# adder.net
KiCad netlist of a schematic drawn in EAGLE
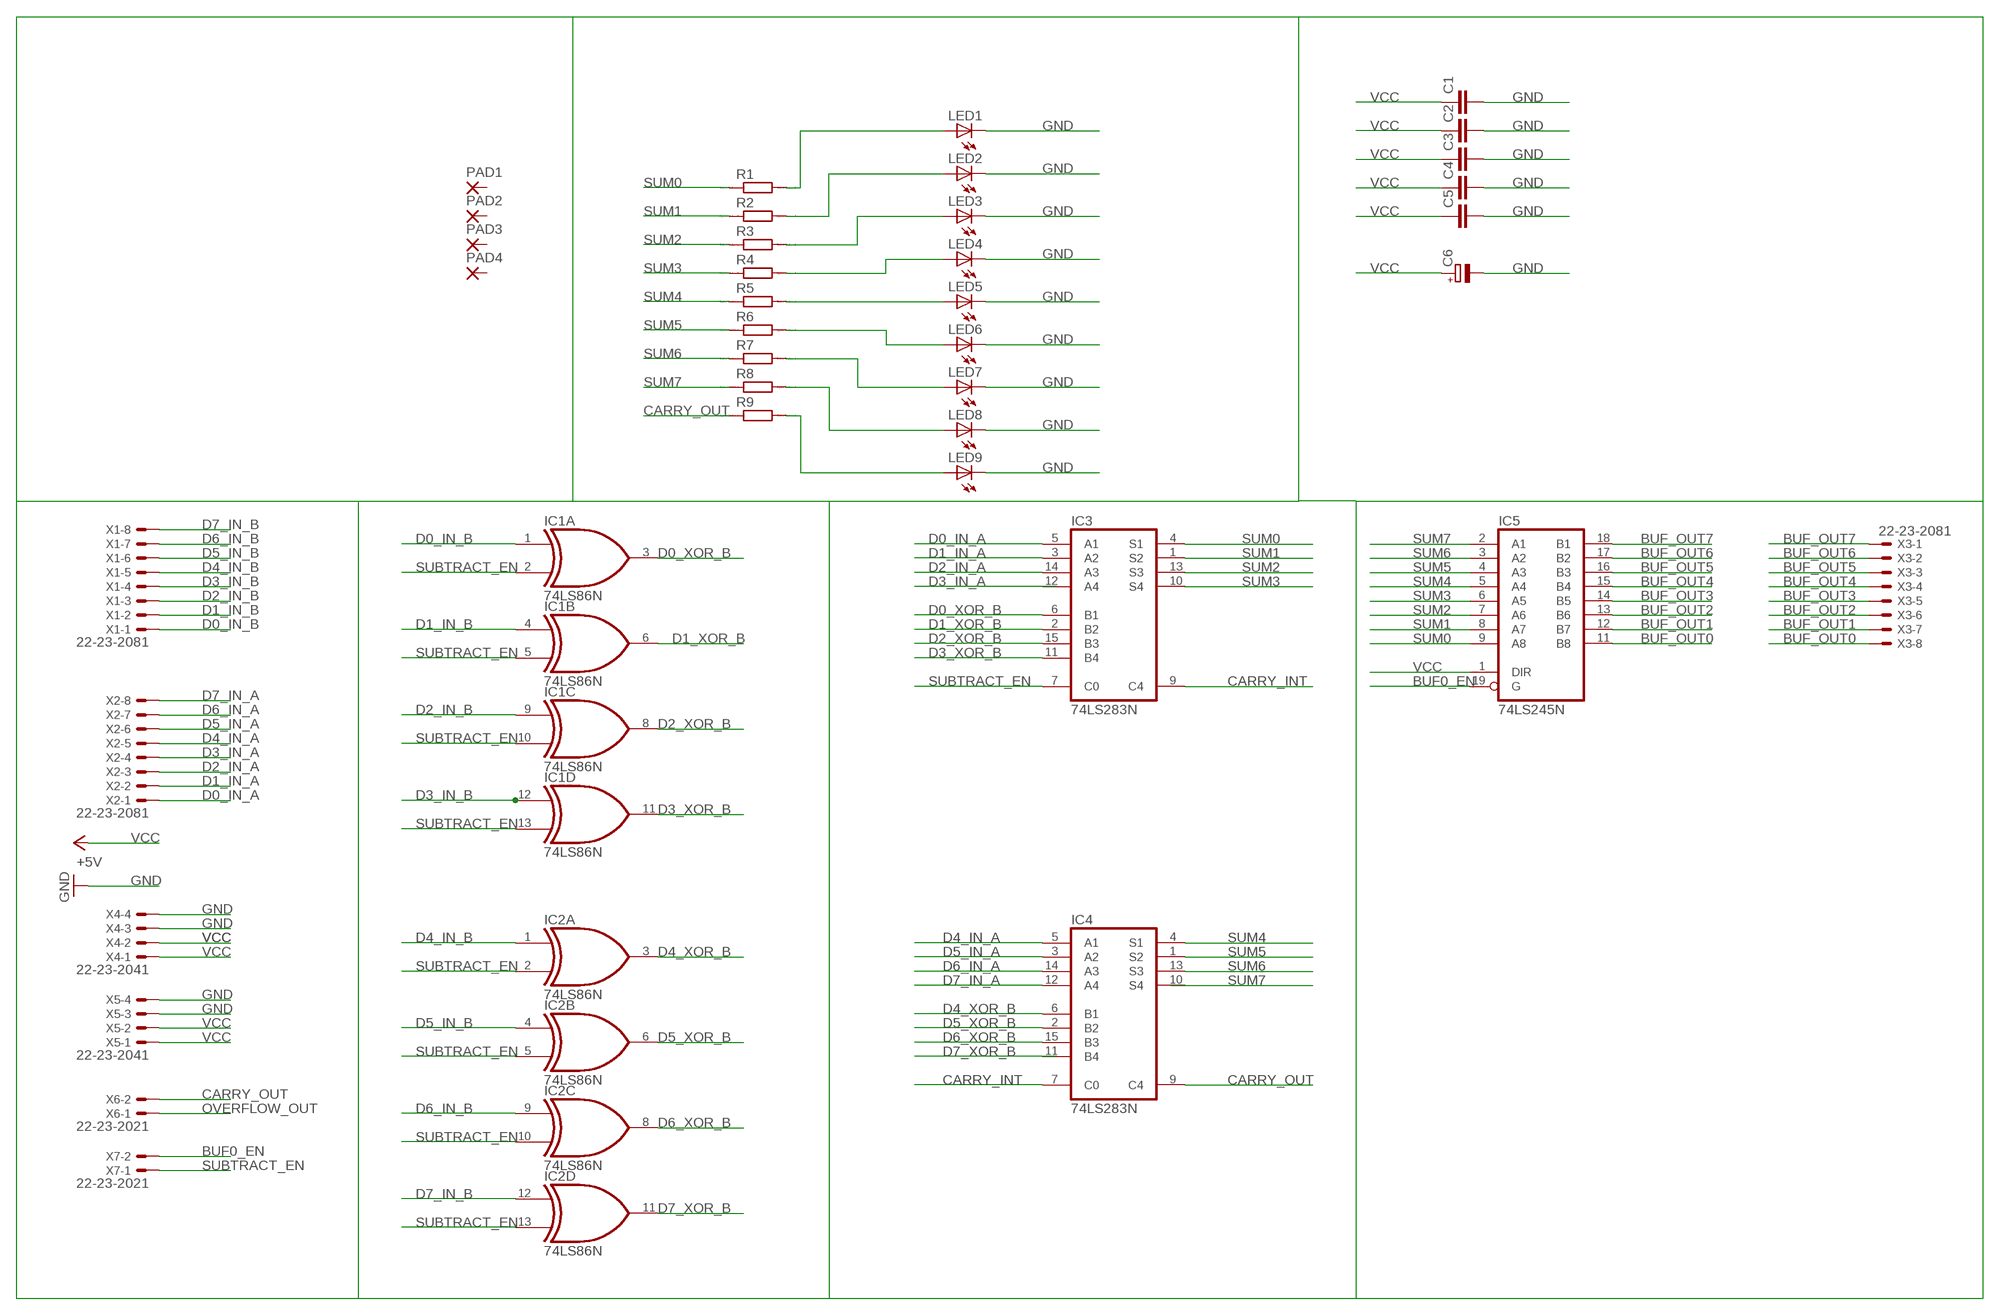
[diagram p0: schematic, sheet 1]

(export (version "E")
  (design (tool "Eeschema 10.0.6"))
  (components
    (comp (ref "C1")
      (value "C-EU025-025X050")
      (footprint "eagle-import:C025-025X050")
      (libsource (lib "eagle-import") (part "C-EU025-025X050"))
    )
    (comp (ref "C2")
      (value "C-EU025-025X050")
      (footprint "eagle-import:C025-025X050")
      (libsource (lib "eagle-import") (part "C-EU025-025X050"))
    )
    (comp (ref "C3")
      (value "C-EU025-025X050")
      (footprint "eagle-import:C025-025X050")
      (libsource (lib "eagle-import") (part "C-EU025-025X050"))
    )
    (comp (ref "C4")
      (value "C-EU025-025X050")
      (footprint "eagle-import:C025-025X050")
      (libsource (lib "eagle-import") (part "C-EU025-025X050"))
    )
    (comp (ref "C5")
      (value "C-EU025-025X050")
      (footprint "eagle-import:C025-025X050")
      (libsource (lib "eagle-import") (part "C-EU025-025X050"))
    )
    (comp (ref "C6")
      (value "CPOL-EUE2.5-6")
      (footprint "eagle-import:E2,5-6")
      (libsource (lib "eagle-import") (part "CPOL-EUE2.5-6"))
    )
    (comp (ref "IC1")
      (value "74LS86N")
      (footprint "eagle-import:DIL14")
      (libsource (lib "eagle-import") (part "7486NLS"))
    )
    (comp (ref "IC2")
      (value "74LS86N")
      (footprint "eagle-import:DIL14")
      (libsource (lib "eagle-import") (part "7486NLS"))
    )
    (comp (ref "IC3")
      (value "74LS283N")
      (footprint "eagle-import:DIL16")
      (libsource (lib "eagle-import") (part "74283NLS"))
    )
    (comp (ref "IC4")
      (value "74LS283N")
      (footprint "eagle-import:DIL16")
      (libsource (lib "eagle-import") (part "74283NLS"))
    )
    (comp (ref "IC5")
      (value "74LS245N")
      (footprint "eagle-import:DIL20")
      (libsource (lib "eagle-import") (part "74245NLS"))
    )
    (comp (ref "LED1")
      (value "LED5MM")
      (footprint "eagle-import:LED5MM")
      (libsource (lib "eagle-import") (part "LED5MM"))
    )
    (comp (ref "LED2")
      (value "LED5MM")
      (footprint "eagle-import:LED5MM")
      (libsource (lib "eagle-import") (part "LED5MM"))
    )
    (comp (ref "LED3")
      (value "LED5MM")
      (footprint "eagle-import:LED5MM")
      (libsource (lib "eagle-import") (part "LED5MM"))
    )
    (comp (ref "LED4")
      (value "LED5MM")
      (footprint "eagle-import:LED5MM")
      (libsource (lib "eagle-import") (part "LED5MM"))
    )
    (comp (ref "LED5")
      (value "LED5MM")
      (footprint "eagle-import:LED5MM")
      (libsource (lib "eagle-import") (part "LED5MM"))
    )
    (comp (ref "LED6")
      (value "LED5MM")
      (footprint "eagle-import:LED5MM")
      (libsource (lib "eagle-import") (part "LED5MM"))
    )
    (comp (ref "LED7")
      (value "LED5MM")
      (footprint "eagle-import:LED5MM")
      (libsource (lib "eagle-import") (part "LED5MM"))
    )
    (comp (ref "LED8")
      (value "LED5MM")
      (footprint "eagle-import:LED5MM")
      (libsource (lib "eagle-import") (part "LED5MM"))
    )
    (comp (ref "LED9")
      (value "LED5MM")
      (footprint "eagle-import:LED5MM")
      (libsource (lib "eagle-import") (part "LED5MM"))
    )
    (comp (ref "PAD1")
      (value "3,17/1,3")
      (footprint "eagle-import:3,17_1,3")
      (libsource (lib "eagle-import") (part "3,17/1,3"))
    )
    (comp (ref "PAD2")
      (value "3,17/1,3")
      (footprint "eagle-import:3,17_1,3")
      (libsource (lib "eagle-import") (part "3,17/1,3"))
    )
    (comp (ref "PAD3")
      (value "3,17/1,3")
      (footprint "eagle-import:3,17_1,3")
      (libsource (lib "eagle-import") (part "3,17/1,3"))
    )
    (comp (ref "PAD4")
      (value "3,17/1,3")
      (footprint "eagle-import:3,17_1,3")
      (libsource (lib "eagle-import") (part "3,17/1,3"))
    )
    (comp (ref "R1")
      (value "R0207/10")
      (footprint "eagle-import:0207_10")
      (libsource (lib "eagle-import") (part "R0207/10"))
    )
    (comp (ref "R2")
      (value "R0207/10")
      (footprint "eagle-import:0207_10")
      (libsource (lib "eagle-import") (part "R0207/10"))
    )
    (comp (ref "R3")
      (value "R0207/10")
      (footprint "eagle-import:0207_10")
      (libsource (lib "eagle-import") (part "R0207/10"))
    )
    (comp (ref "R4")
      (value "R0207/10")
      (footprint "eagle-import:0207_10")
      (libsource (lib "eagle-import") (part "R0207/10"))
    )
    (comp (ref "R5")
      (value "R0207/10")
      (footprint "eagle-import:0207_10")
      (libsource (lib "eagle-import") (part "R0207/10"))
    )
    (comp (ref "R6")
      (value "R0207/10")
      (footprint "eagle-import:0207_10")
      (libsource (lib "eagle-import") (part "R0207/10"))
    )
    (comp (ref "R7")
      (value "R0207/10")
      (footprint "eagle-import:0207_10")
      (libsource (lib "eagle-import") (part "R0207/10"))
    )
    (comp (ref "R8")
      (value "R0207/10")
      (footprint "eagle-import:0207_10")
      (libsource (lib "eagle-import") (part "R0207/10"))
    )
    (comp (ref "R9")
      (value "R0207/10")
      (footprint "eagle-import:0207_10")
      (libsource (lib "eagle-import") (part "R0207/10"))
    )
    (comp (ref "X1")
      (value "22-23-2081")
      (footprint "eagle-import:22-23-2081")
      (fields (field (name "MF") "MOLEX"))
      (libsource (lib "eagle-import") (part "22-23-2081"))
    )
    (comp (ref "X2")
      (value "22-23-2081")
      (footprint "eagle-import:22-23-2081")
      (fields (field (name "MF") "MOLEX"))
      (libsource (lib "eagle-import") (part "22-23-2081"))
    )
    (comp (ref "X3")
      (value "22-23-2081")
      (footprint "eagle-import:22-23-2081")
      (fields (field (name "MF") "MOLEX"))
      (libsource (lib "eagle-import") (part "22-23-2081"))
    )
    (comp (ref "X4")
      (value "22-23-2041")
      (footprint "eagle-import:22-23-2041")
      (fields (field (name "MF") "MOLEX"))
      (libsource (lib "eagle-import") (part "22-23-2041"))
    )
    (comp (ref "X5")
      (value "22-23-2041")
      (footprint "eagle-import:22-23-2041")
      (fields (field (name "MF") "MOLEX"))
      (libsource (lib "eagle-import") (part "22-23-2041"))
    )
    (comp (ref "X6")
      (value "22-23-2021")
      (footprint "eagle-import:22-23-2021")
      (fields (field (name "MF") "MOLEX"))
      (libsource (lib "eagle-import") (part "22-23-2021"))
    )
    (comp (ref "X7")
      (value "22-23-2021")
      (footprint "eagle-import:22-23-2021")
      (fields (field (name "MF") "MOLEX"))
      (libsource (lib "eagle-import") (part "22-23-2021"))
    )
  )
  (nets
    (net (code "1") (name "+5V") (class "Default")
      (node (ref "C1") (pin "1") (pinfunction "1_1") (pintype "passive"))
      (node (ref "C2") (pin "1") (pinfunction "1_1") (pintype "passive"))
      (node (ref "C3") (pin "1") (pinfunction "1_1") (pintype "passive"))
      (node (ref "C4") (pin "1") (pinfunction "1_1") (pintype "passive"))
      (node (ref "C5") (pin "1") (pinfunction "1_1") (pintype "passive"))
      (node (ref "C6") (pin "+") (pinfunction "+_+") (pintype "passive"))
      (node (ref "IC5") (pin "1") (pinfunction "DIR_1") (pintype "input"))
      (node (ref "X4") (pin "1") (pinfunction "S_1") (pintype "passive"))
      (node (ref "X4") (pin "2") (pinfunction "S_2") (pintype "passive"))
      (node (ref "X5") (pin "1") (pinfunction "S_1") (pintype "passive"))
      (node (ref "X5") (pin "2") (pinfunction "S_2") (pintype "passive"))
    )
    (net (code "2") (name "/BUF0_EN") (class "Default")
      (node (ref "IC5") (pin "19") (pinfunction "G_19") (pintype "input"))
      (node (ref "X7") (pin "2") (pinfunction "S_2") (pintype "passive"))
    )
    (net (code "3") (name "/BUF_OUT0") (class "Default")
      (node (ref "IC5") (pin "11") (pinfunction "B8_11") (pintype "bidirectional"))
      (node (ref "X3") (pin "8") (pinfunction "S_8") (pintype "passive"))
    )
    (net (code "4") (name "/BUF_OUT1") (class "Default")
      (node (ref "IC5") (pin "12") (pinfunction "B7_12") (pintype "bidirectional"))
      (node (ref "X3") (pin "7") (pinfunction "S_7") (pintype "passive"))
    )
    (net (code "5") (name "/BUF_OUT2") (class "Default")
      (node (ref "IC5") (pin "13") (pinfunction "B6_13") (pintype "bidirectional"))
      (node (ref "X3") (pin "6") (pinfunction "S_6") (pintype "passive"))
    )
    (net (code "6") (name "/BUF_OUT3") (class "Default")
      (node (ref "IC5") (pin "14") (pinfunction "B5_14") (pintype "bidirectional"))
      (node (ref "X3") (pin "5") (pinfunction "S_5") (pintype "passive"))
    )
    (net (code "7") (name "/BUF_OUT4") (class "Default")
      (node (ref "IC5") (pin "15") (pinfunction "B4_15") (pintype "bidirectional"))
      (node (ref "X3") (pin "4") (pinfunction "S_4") (pintype "passive"))
    )
    (net (code "8") (name "/BUF_OUT5") (class "Default")
      (node (ref "IC5") (pin "16") (pinfunction "B3_16") (pintype "bidirectional"))
      (node (ref "X3") (pin "3") (pinfunction "S_3") (pintype "passive"))
    )
    (net (code "9") (name "/BUF_OUT6") (class "Default")
      (node (ref "IC5") (pin "17") (pinfunction "B2_17") (pintype "bidirectional"))
      (node (ref "X3") (pin "2") (pinfunction "S_2") (pintype "passive"))
    )
    (net (code "10") (name "/BUF_OUT7") (class "Default")
      (node (ref "IC5") (pin "18") (pinfunction "B1_18") (pintype "bidirectional"))
      (node (ref "X3") (pin "1") (pinfunction "S_1") (pintype "passive"))
    )
    (net (code "11") (name "/CARRY_INT") (class "Default")
      (node (ref "IC3") (pin "9") (pinfunction "C4_9") (pintype "output"))
      (node (ref "IC4") (pin "7") (pinfunction "C0_7") (pintype "input"))
    )
    (net (code "12") (name "/CARRY_OUT") (class "Default")
      (node (ref "IC4") (pin "9") (pinfunction "C4_9") (pintype "output"))
      (node (ref "R9") (pin "1") (pinfunction "1_1") (pintype "passive"))
      (node (ref "X6") (pin "2") (pinfunction "S_2") (pintype "passive"))
    )
    (net (code "13") (name "/D0_IN_A") (class "Default")
      (node (ref "IC3") (pin "5") (pinfunction "A1_5") (pintype "input"))
      (node (ref "X2") (pin "1") (pinfunction "S_1") (pintype "passive"))
    )
    (net (code "14") (name "/D0_IN_B") (class "Default")
      (node (ref "IC1") (pin "1") (pinfunction "I0_1") (pintype "input"))
      (node (ref "X1") (pin "1") (pinfunction "S_1") (pintype "passive"))
    )
    (net (code "15") (name "/D0_XOR_B") (class "Default")
      (node (ref "IC1") (pin "3") (pinfunction "O_3") (pintype "output"))
      (node (ref "IC3") (pin "6") (pinfunction "B1_6") (pintype "input"))
    )
    (net (code "16") (name "/D1_IN_A") (class "Default")
      (node (ref "IC3") (pin "3") (pinfunction "A2_3") (pintype "input"))
      (node (ref "X2") (pin "2") (pinfunction "S_2") (pintype "passive"))
    )
    (net (code "17") (name "/D1_IN_B") (class "Default")
      (node (ref "IC1") (pin "4") (pinfunction "I0_4") (pintype "input"))
      (node (ref "X1") (pin "2") (pinfunction "S_2") (pintype "passive"))
    )
    (net (code "18") (name "/D1_XOR_B") (class "Default")
      (node (ref "IC1") (pin "6") (pinfunction "O_6") (pintype "output"))
      (node (ref "IC3") (pin "2") (pinfunction "B2_2") (pintype "input"))
    )
    (net (code "19") (name "/D2_IN_A") (class "Default")
      (node (ref "IC3") (pin "14") (pinfunction "A3_14") (pintype "input"))
      (node (ref "X2") (pin "3") (pinfunction "S_3") (pintype "passive"))
    )
    (net (code "20") (name "/D2_IN_B") (class "Default")
      (node (ref "IC1") (pin "9") (pinfunction "I0_9") (pintype "input"))
      (node (ref "X1") (pin "3") (pinfunction "S_3") (pintype "passive"))
    )
    (net (code "21") (name "/D2_XOR_B") (class "Default")
      (node (ref "IC1") (pin "8") (pinfunction "O_8") (pintype "output"))
      (node (ref "IC3") (pin "15") (pinfunction "B3_15") (pintype "input"))
    )
    (net (code "22") (name "/D3_IN_A") (class "Default")
      (node (ref "X2") (pin "4") (pinfunction "S_4") (pintype "passive"))
    )
    (net (code "23") (name "/D3_IN_B") (class "Default")
      (node (ref "IC1") (pin "12") (pinfunction "I0_12") (pintype "input"))
      (node (ref "X1") (pin "4") (pinfunction "S_4") (pintype "passive"))
    )
    (net (code "24") (name "/D3_XOR_B") (class "Default")
      (node (ref "IC1") (pin "11") (pinfunction "O_11") (pintype "output"))
      (node (ref "IC3") (pin "11") (pinfunction "B4_11") (pintype "input"))
    )
    (net (code "25") (name "/D4_IN_A") (class "Default")
      (node (ref "IC4") (pin "5") (pinfunction "A1_5") (pintype "input"))
      (node (ref "X2") (pin "5") (pinfunction "S_5") (pintype "passive"))
    )
    (net (code "26") (name "/D4_IN_B") (class "Default")
      (node (ref "IC2") (pin "1") (pinfunction "I0_1") (pintype "input"))
      (node (ref "X1") (pin "5") (pinfunction "S_5") (pintype "passive"))
    )
    (net (code "27") (name "/D4_XOR_B") (class "Default")
      (node (ref "IC2") (pin "3") (pinfunction "O_3") (pintype "output"))
      (node (ref "IC4") (pin "6") (pinfunction "B1_6") (pintype "input"))
    )
    (net (code "28") (name "/D5_IN_A") (class "Default")
      (node (ref "IC4") (pin "3") (pinfunction "A2_3") (pintype "input"))
      (node (ref "X2") (pin "6") (pinfunction "S_6") (pintype "passive"))
    )
    (net (code "29") (name "/D5_IN_B") (class "Default")
      (node (ref "IC2") (pin "4") (pinfunction "I0_4") (pintype "input"))
      (node (ref "X1") (pin "6") (pinfunction "S_6") (pintype "passive"))
    )
    (net (code "30") (name "/D5_XOR_B") (class "Default")
      (node (ref "IC2") (pin "6") (pinfunction "O_6") (pintype "output"))
      (node (ref "IC4") (pin "2") (pinfunction "B2_2") (pintype "input"))
    )
    (net (code "31") (name "/D6_IN_A") (class "Default")
      (node (ref "IC4") (pin "14") (pinfunction "A3_14") (pintype "input"))
      (node (ref "X2") (pin "7") (pinfunction "S_7") (pintype "passive"))
    )
    (net (code "32") (name "/D6_IN_B") (class "Default")
      (node (ref "IC2") (pin "9") (pinfunction "I0_9") (pintype "input"))
      (node (ref "X1") (pin "7") (pinfunction "S_7") (pintype "passive"))
    )
    (net (code "33") (name "/D6_XOR_B") (class "Default")
      (node (ref "IC2") (pin "8") (pinfunction "O_8") (pintype "output"))
      (node (ref "IC4") (pin "15") (pinfunction "B3_15") (pintype "input"))
    )
    (net (code "34") (name "/D7_IN_A") (class "Default")
      (node (ref "IC4") (pin "12") (pinfunction "A4_12") (pintype "input"))
      (node (ref "X2") (pin "8") (pinfunction "S_8") (pintype "passive"))
    )
    (net (code "35") (name "/D7_IN_B") (class "Default")
      (node (ref "IC2") (pin "12") (pinfunction "I0_12") (pintype "input"))
      (node (ref "X1") (pin "8") (pinfunction "S_8") (pintype "passive"))
    )
    (net (code "36") (name "/D7_XOR_B") (class "Default")
      (node (ref "IC2") (pin "11") (pinfunction "O_11") (pintype "output"))
    )
    (net (code "37") (name "/OVERFLOW_OUT") (class "Default")
      (node (ref "X6") (pin "1") (pinfunction "S_1") (pintype "passive"))
    )
    (net (code "38") (name "/SUBTRACT_EN") (class "Default")
      (node (ref "IC1") (pin "10") (pinfunction "I1_10") (pintype "input"))
      (node (ref "IC1") (pin "13") (pinfunction "I1_13") (pintype "input"))
      (node (ref "IC1") (pin "2") (pinfunction "I1_2") (pintype "input"))
      (node (ref "IC1") (pin "5") (pinfunction "I1_5") (pintype "input"))
      (node (ref "IC2") (pin "10") (pinfunction "I1_10") (pintype "input"))
      (node (ref "IC2") (pin "13") (pinfunction "I1_13") (pintype "input"))
      (node (ref "IC2") (pin "2") (pinfunction "I1_2") (pintype "input"))
      (node (ref "IC2") (pin "5") (pinfunction "I1_5") (pintype "input"))
      (node (ref "IC3") (pin "7") (pinfunction "C0_7") (pintype "input"))
      (node (ref "X7") (pin "1") (pinfunction "S_1") (pintype "passive"))
    )
    (net (code "39") (name "/SUM0") (class "Default")
      (node (ref "IC3") (pin "4") (pinfunction "S1_4") (pintype "output"))
      (node (ref "IC5") (pin "9") (pinfunction "A8_9") (pintype "bidirectional"))
      (node (ref "R1") (pin "1") (pinfunction "1_1") (pintype "passive"))
    )
    (net (code "40") (name "/SUM1") (class "Default")
      (node (ref "IC3") (pin "1") (pinfunction "S2_1") (pintype "output"))
      (node (ref "IC5") (pin "8") (pinfunction "A7_8") (pintype "bidirectional"))
      (node (ref "R2") (pin "1") (pinfunction "1_1") (pintype "passive"))
    )
    (net (code "41") (name "/SUM2") (class "Default")
      (node (ref "IC3") (pin "13") (pinfunction "S3_13") (pintype "output"))
      (node (ref "IC5") (pin "7") (pinfunction "A6_7") (pintype "bidirectional"))
      (node (ref "R3") (pin "1") (pinfunction "1_1") (pintype "passive"))
    )
    (net (code "42") (name "/SUM3") (class "Default")
      (node (ref "IC3") (pin "10") (pinfunction "S4_10") (pintype "output"))
      (node (ref "IC5") (pin "6") (pinfunction "A5_6") (pintype "bidirectional"))
      (node (ref "R4") (pin "1") (pinfunction "1_1") (pintype "passive"))
    )
    (net (code "43") (name "/SUM4") (class "Default")
      (node (ref "IC4") (pin "4") (pinfunction "S1_4") (pintype "output"))
      (node (ref "IC5") (pin "5") (pinfunction "A4_5") (pintype "bidirectional"))
      (node (ref "R5") (pin "1") (pinfunction "1_1") (pintype "passive"))
    )
    (net (code "44") (name "/SUM5") (class "Default")
      (node (ref "IC4") (pin "1") (pinfunction "S2_1") (pintype "output"))
      (node (ref "IC5") (pin "4") (pinfunction "A3_4") (pintype "bidirectional"))
      (node (ref "R6") (pin "1") (pinfunction "1_1") (pintype "passive"))
    )
    (net (code "45") (name "/SUM6") (class "Default")
      (node (ref "IC4") (pin "13") (pinfunction "S3_13") (pintype "output"))
      (node (ref "IC5") (pin "3") (pinfunction "A2_3") (pintype "bidirectional"))
      (node (ref "R7") (pin "1") (pinfunction "1_1") (pintype "passive"))
    )
    (net (code "46") (name "/SUM7") (class "Default")
      (node (ref "IC5") (pin "2") (pinfunction "A1_2") (pintype "bidirectional"))
      (node (ref "R8") (pin "1") (pinfunction "1_1") (pintype "passive"))
    )
    (net (code "47") (name "GND") (class "Default")
      (node (ref "C1") (pin "2") (pinfunction "2_2") (pintype "passive"))
      (node (ref "C2") (pin "2") (pinfunction "2_2") (pintype "passive"))
      (node (ref "C3") (pin "2") (pinfunction "2_2") (pintype "passive"))
      (node (ref "C4") (pin "2") (pinfunction "2_2") (pintype "passive"))
      (node (ref "C5") (pin "2") (pinfunction "2_2") (pintype "passive"))
      (node (ref "C6") (pin "-") (pinfunction "-_-") (pintype "passive"))
      (node (ref "LED1") (pin "K") (pinfunction "C_K") (pintype "passive"))
      (node (ref "LED2") (pin "K") (pinfunction "C_K") (pintype "passive"))
      (node (ref "LED3") (pin "K") (pinfunction "C_K") (pintype "passive"))
      (node (ref "LED4") (pin "K") (pinfunction "C_K") (pintype "passive"))
      (node (ref "LED5") (pin "K") (pinfunction "C_K") (pintype "passive"))
      (node (ref "LED6") (pin "K") (pinfunction "C_K") (pintype "passive"))
      (node (ref "LED7") (pin "K") (pinfunction "C_K") (pintype "passive"))
      (node (ref "LED8") (pin "K") (pinfunction "C_K") (pintype "passive"))
      (node (ref "LED9") (pin "K") (pinfunction "C_K") (pintype "passive"))
      (node (ref "X4") (pin "3") (pinfunction "S_3") (pintype "passive"))
      (node (ref "X4") (pin "4") (pinfunction "S_4") (pintype "passive"))
      (node (ref "X5") (pin "3") (pinfunction "S_3") (pintype "passive"))
      (node (ref "X5") (pin "4") (pinfunction "S_4") (pintype "passive"))
    )
    (net (code "48") (name "Net-(LED1-PadA)") (class "Default")
      (node (ref "LED1") (pin "A") (pinfunction "A_A") (pintype "passive"))
      (node (ref "R1") (pin "2") (pinfunction "2_2") (pintype "passive"))
    )
    (net (code "49") (name "Net-(LED2-PadA)") (class "Default")
      (node (ref "LED2") (pin "A") (pinfunction "A_A") (pintype "passive"))
      (node (ref "R2") (pin "2") (pinfunction "2_2") (pintype "passive"))
    )
    (net (code "50") (name "Net-(LED3-PadA)") (class "Default")
      (node (ref "LED3") (pin "A") (pinfunction "A_A") (pintype "passive"))
      (node (ref "R3") (pin "2") (pinfunction "2_2") (pintype "passive"))
    )
    (net (code "51") (name "Net-(LED4-PadA)") (class "Default")
      (node (ref "LED4") (pin "A") (pinfunction "A_A") (pintype "passive"))
      (node (ref "R4") (pin "2") (pinfunction "2_2") (pintype "passive"))
    )
    (net (code "52") (name "Net-(LED5-PadA)") (class "Default")
      (node (ref "LED5") (pin "A") (pinfunction "A_A") (pintype "passive"))
      (node (ref "R5") (pin "2") (pinfunction "2_2") (pintype "passive"))
    )
    (net (code "53") (name "Net-(LED6-PadA)") (class "Default")
      (node (ref "LED6") (pin "A") (pinfunction "A_A") (pintype "passive"))
      (node (ref "R6") (pin "2") (pinfunction "2_2") (pintype "passive"))
    )
    (net (code "54") (name "Net-(LED7-PadA)") (class "Default")
      (node (ref "LED7") (pin "A") (pinfunction "A_A") (pintype "passive"))
      (node (ref "R7") (pin "2") (pinfunction "2_2") (pintype "passive"))
    )
    (net (code "55") (name "Net-(LED8-PadA)") (class "Default")
      (node (ref "LED8") (pin "A") (pinfunction "A_A") (pintype "passive"))
      (node (ref "R8") (pin "2") (pinfunction "2_2") (pintype "passive"))
    )
    (net (code "56") (name "Net-(LED9-PadA)") (class "Default")
      (node (ref "LED9") (pin "A") (pinfunction "A_A") (pintype "passive"))
      (node (ref "R9") (pin "2") (pinfunction "2_2") (pintype "passive"))
    )
    (net (code "57") (name "unconnected-(IC3A-A4-Pad12)") (class "Default")
      (node (ref "IC3") (pin "12") (pinfunction "A4_12") (pintype "input"))
    )
    (net (code "58") (name "unconnected-(IC4A-B4-Pad11)") (class "Default")
      (node (ref "IC4") (pin "11") (pinfunction "B4_11") (pintype "input"))
    )
    (net (code "59") (name "unconnected-(IC4A-S4-Pad10)") (class "Default")
      (node (ref "IC4") (pin "10") (pinfunction "S4_10") (pintype "output"))
    )
    (net (code "60") (name "unconnected-(PAD1-P-Pad1)") (class "Default")
      (node (ref "PAD1") (pin "1") (pinfunction "P_1") (pintype "passive"))
    )
    (net (code "61") (name "unconnected-(PAD2-P-Pad1)") (class "Default")
      (node (ref "PAD2") (pin "1") (pinfunction "P_1") (pintype "passive"))
    )
    (net (code "62") (name "unconnected-(PAD3-P-Pad1)") (class "Default")
      (node (ref "PAD3") (pin "1") (pinfunction "P_1") (pintype "passive"))
    )
    (net (code "63") (name "unconnected-(PAD4-P-Pad1)") (class "Default")
      (node (ref "PAD4") (pin "1") (pinfunction "P_1") (pintype "passive"))
    )
  )
)
